# 467444_130_3_5.net
KiCad netlist of a schematic drawn in Altium Designer
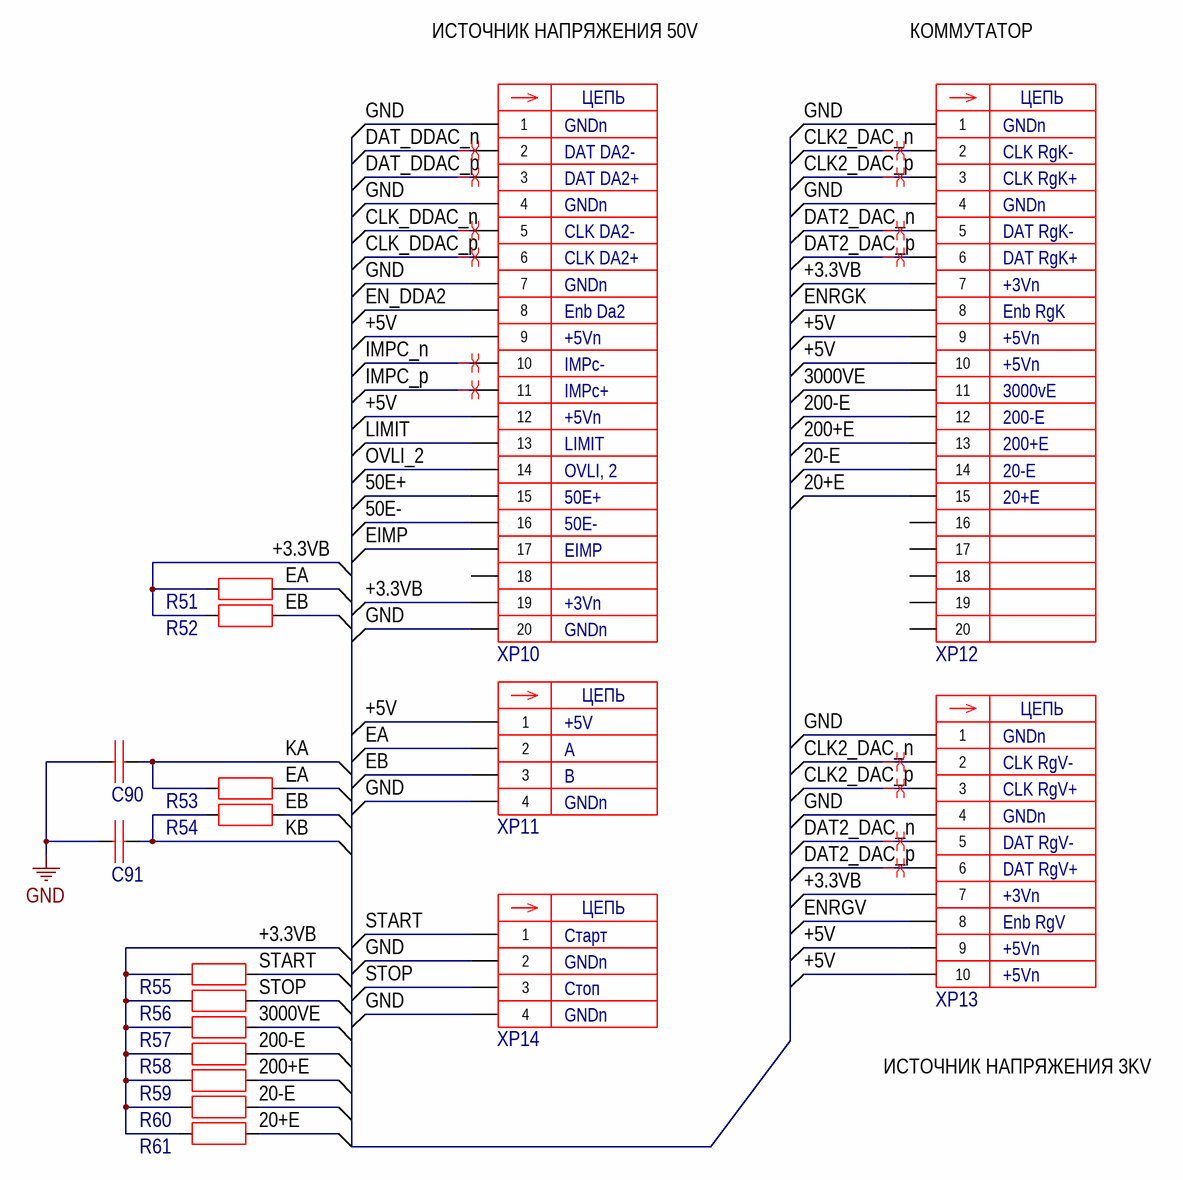
[diagram p0: УШЯИ.467444.130Э3_5.SchDoc]

(export (version "E")
  (design (tool "Eeschema 10.0.6"))
  (components
    (comp (ref "C90")
      (value "0,1 µF")
      (footprint "C_0805 [2012 Metric]")
      (description "Неполярный конденсатор")
      (fields (field (name "MANUFACTURER") "Murata") (field (name "VOLTAGE") "50V"))
      (libsource (lib "lib") (part "C_const"))
    )
    (comp (ref "C91")
      (value "0,1 µF")
      (footprint "C_0805 [2012 Metric]")
      (description "Неполярный конденсатор")
      (fields (field (name "MANUFACTURER") "Murata") (field (name "VOLTAGE") "50V"))
      (libsource (lib "lib") (part "C_const"))
    )
    (comp (ref "R51")
      (value "10k")
      (footprint "R_0805 [2012 Metric]")
      (fields (field (name "TOLERANCE") "±1%"))
      (libsource (lib "lib") (part "R_Const"))
    )
    (comp (ref "R52")
      (value "10k")
      (footprint "R_0805 [2012 Metric]")
      (fields (field (name "TOLERANCE") "±1%"))
      (libsource (lib "lib") (part "R_Const"))
    )
    (comp (ref "R53")
      (value "10k")
      (footprint "R_0805 [2012 Metric]")
      (fields (field (name "TOLERANCE") "±1%"))
      (libsource (lib "lib") (part "R_Const"))
    )
    (comp (ref "R54")
      (value "10k")
      (footprint "R_0805 [2012 Metric]")
      (fields (field (name "TOLERANCE") "±1%"))
      (libsource (lib "lib") (part "R_Const"))
    )
    (comp (ref "R55")
      (value "10k")
      (footprint "R_0805 [2012 Metric]")
      (fields (field (name "TOLERANCE") "±1%"))
      (libsource (lib "lib") (part "R_Const"))
    )
    (comp (ref "R56")
      (value "10k")
      (footprint "R_0805 [2012 Metric]")
      (fields (field (name "TOLERANCE") "±1%"))
      (libsource (lib "lib") (part "R_Const"))
    )
    (comp (ref "R57")
      (value "10k")
      (footprint "R_0805 [2012 Metric]")
      (fields (field (name "TOLERANCE") "±1%"))
      (libsource (lib "lib") (part "R_Const"))
    )
    (comp (ref "R58")
      (value "10k")
      (footprint "R_0805 [2012 Metric]")
      (fields (field (name "TOLERANCE") "±1%"))
      (libsource (lib "lib") (part "R_Const"))
    )
    (comp (ref "R59")
      (value "10k")
      (footprint "R_0805 [2012 Metric]")
      (fields (field (name "TOLERANCE") "±1%"))
      (libsource (lib "lib") (part "R_Const"))
    )
    (comp (ref "R60")
      (value "10k")
      (footprint "R_0805 [2012 Metric]")
      (fields (field (name "TOLERANCE") "±1%"))
      (libsource (lib "lib") (part "R_Const"))
    )
    (comp (ref "R61")
      (value "10k")
      (footprint "R_0805 [2012 Metric]")
      (fields (field (name "TOLERANCE") "±1%"))
      (libsource (lib "lib") (part "R_Const"))
    )
    (comp (ref "XP10")
      (value "BH2-20R")
      (footprint "BH2-20R")
      (description "Male, 20 pins, 2 rows, Right Angle, DS1014-20RF1B-B, 2 mm")
      (fields (field (name "MANUFACTURER") "Connfly electronic"))
      (libsource (lib "lib") (part "M_20"))
    )
    (comp (ref "XP11")
      (value "AMPMODU II 280371-2")
      (footprint "AMP II-280371-2")
      (description "Male, 4 pin, 1 row, Vertical, Board-to-Board, 2.54 mm")
      (fields (field (name "MANUFACTURER") "TE Connectivity"))
      (libsource (lib "lib") (part "M_4"))
    )
    (comp (ref "XP12")
      (value "BH2-20R")
      (footprint "BH2-20R")
      (description "Male, 20 pins, 2 rows, Right Angle, DS1014-20RF1B-B, 2 mm")
      (fields (field (name "MANUFACTURER") "Connfly electronic"))
      (libsource (lib "lib") (part "M_20"))
    )
    (comp (ref "XP13")
      (value "BH2-10R")
      (footprint "BH2-10R")
      (description "Male, 10 pins, 2 rows, Vertical, DS1014-10RF1B-B, 2 mm")
      (fields (field (name "MANUFACTURER") "Connfly electronic"))
      (libsource (lib "lib") (part "M_10"))
    )
    (comp (ref "XP14")
      (value "AMPMODU II 280371-2")
      (footprint "AMP II-280371-2")
      (description "Male, 4 pin, 1 row, Vertical, Board-to-Board, 2.54 mm")
      (fields (field (name "MANUFACTURER") "TE Connectivity"))
      (libsource (lib "lib") (part "M_4"))
    )
  )
  (nets
    (net (code "1") (name "/+3.3VB") (class "Default")
      (node (ref "R51") (pin "1") (pinfunction "1_1") (pintype "passive"))
      (node (ref "R52") (pin "1") (pinfunction "1_1") (pintype "passive"))
      (node (ref "R55") (pin "1") (pinfunction "1_1") (pintype "passive"))
      (node (ref "R56") (pin "1") (pinfunction "1_1") (pintype "passive"))
      (node (ref "R57") (pin "1") (pinfunction "1_1") (pintype "passive"))
      (node (ref "R58") (pin "1") (pinfunction "1_1") (pintype "passive"))
      (node (ref "R59") (pin "1") (pinfunction "1_1") (pintype "passive"))
      (node (ref "R60") (pin "1") (pinfunction "1_1") (pintype "passive"))
      (node (ref "R61") (pin "1") (pinfunction "1_1") (pintype "passive"))
      (node (ref "XP10") (pin "19") (pinfunction "19_19") (pintype "passive"))
      (node (ref "XP12") (pin "7") (pinfunction "7_7") (pintype "passive"))
      (node (ref "XP13") (pin "7") (pinfunction "7_7") (pintype "passive"))
    )
    (net (code "2") (name "/+5V") (class "Default")
      (node (ref "XP10") (pin "12") (pinfunction "12_12") (pintype "passive"))
      (node (ref "XP10") (pin "9") (pinfunction "9_9") (pintype "passive"))
      (node (ref "XP11") (pin "1") (pinfunction "1_1") (pintype "passive"))
      (node (ref "XP12") (pin "10") (pinfunction "10_10") (pintype "passive"))
      (node (ref "XP12") (pin "9") (pinfunction "9_9") (pintype "passive"))
      (node (ref "XP13") (pin "10") (pinfunction "10_10") (pintype "passive"))
      (node (ref "XP13") (pin "9") (pinfunction "9_9") (pintype "passive"))
    )
    (net (code "3") (name "/20+E") (class "Default")
      (node (ref "R61") (pin "2") (pinfunction "2_2") (pintype "passive"))
      (node (ref "XP12") (pin "15") (pinfunction "15_15") (pintype "passive"))
    )
    (net (code "4") (name "/20-E") (class "Default")
      (node (ref "R60") (pin "2") (pinfunction "2_2") (pintype "passive"))
      (node (ref "XP12") (pin "14") (pinfunction "14_14") (pintype "passive"))
    )
    (net (code "5") (name "/50E+") (class "Default")
      (node (ref "XP10") (pin "15") (pinfunction "15_15") (pintype "passive"))
    )
    (net (code "6") (name "/50E-") (class "Default")
      (node (ref "XP10") (pin "16") (pinfunction "16_16") (pintype "passive"))
    )
    (net (code "7") (name "/200+E") (class "Default")
      (node (ref "R59") (pin "2") (pinfunction "2_2") (pintype "passive"))
      (node (ref "XP12") (pin "13") (pinfunction "13_13") (pintype "passive"))
    )
    (net (code "8") (name "/200-E") (class "Default")
      (node (ref "R58") (pin "2") (pinfunction "2_2") (pintype "passive"))
      (node (ref "XP12") (pin "12") (pinfunction "12_12") (pintype "passive"))
    )
    (net (code "9") (name "/3000VE") (class "Default")
      (node (ref "R57") (pin "2") (pinfunction "2_2") (pintype "passive"))
      (node (ref "XP12") (pin "11") (pinfunction "11_11") (pintype "passive"))
    )
    (net (code "10") (name "/CLK2_DAC_n") (class "Default")
      (node (ref "XP12") (pin "2") (pinfunction "2_2") (pintype "passive"))
      (node (ref "XP13") (pin "2") (pinfunction "2_2") (pintype "passive"))
    )
    (net (code "11") (name "/CLK2_DAC_p") (class "Default")
      (node (ref "XP12") (pin "3") (pinfunction "3_3") (pintype "passive"))
      (node (ref "XP13") (pin "3") (pinfunction "3_3") (pintype "passive"))
    )
    (net (code "12") (name "/CLK_DDAC_n") (class "Default")
      (node (ref "XP10") (pin "5") (pinfunction "5_5") (pintype "passive"))
    )
    (net (code "13") (name "/CLK_DDAC_p") (class "Default")
      (node (ref "XP10") (pin "6") (pinfunction "6_6") (pintype "passive"))
    )
    (net (code "14") (name "/DAT2_DAC_n") (class "Default")
      (node (ref "XP12") (pin "5") (pinfunction "5_5") (pintype "passive"))
      (node (ref "XP13") (pin "5") (pinfunction "5_5") (pintype "passive"))
    )
    (net (code "15") (name "/DAT2_DAC_p") (class "Default")
      (node (ref "XP12") (pin "6") (pinfunction "6_6") (pintype "passive"))
      (node (ref "XP13") (pin "6") (pinfunction "6_6") (pintype "passive"))
    )
    (net (code "16") (name "/DAT_DDAC_n") (class "Default")
      (node (ref "XP10") (pin "2") (pinfunction "2_2") (pintype "passive"))
    )
    (net (code "17") (name "/DAT_DDAC_p") (class "Default")
      (node (ref "XP10") (pin "3") (pinfunction "3_3") (pintype "passive"))
    )
    (net (code "18") (name "/EA") (class "Default")
      (node (ref "R51") (pin "2") (pinfunction "2_2") (pintype "passive"))
      (node (ref "R53") (pin "2") (pinfunction "2_2") (pintype "passive"))
      (node (ref "XP11") (pin "2") (pinfunction "2_2") (pintype "passive"))
    )
    (net (code "19") (name "/EB") (class "Default")
      (node (ref "R52") (pin "2") (pinfunction "2_2") (pintype "passive"))
      (node (ref "R54") (pin "2") (pinfunction "2_2") (pintype "passive"))
      (node (ref "XP11") (pin "3") (pinfunction "3_3") (pintype "passive"))
    )
    (net (code "20") (name "/EIMP") (class "Default")
      (node (ref "XP10") (pin "17") (pinfunction "17_17") (pintype "passive"))
    )
    (net (code "21") (name "/ENRGK") (class "Default")
      (node (ref "XP12") (pin "8") (pinfunction "8_8") (pintype "passive"))
    )
    (net (code "22") (name "/ENRGV") (class "Default")
      (node (ref "XP13") (pin "8") (pinfunction "8_8") (pintype "passive"))
    )
    (net (code "23") (name "/EN_DDA2") (class "Default")
      (node (ref "XP10") (pin "8") (pinfunction "8_8") (pintype "passive"))
    )
    (net (code "24") (name "/IMPC_n") (class "Default")
      (node (ref "XP10") (pin "10") (pinfunction "10_10") (pintype "passive"))
    )
    (net (code "25") (name "/IMPC_p") (class "Default")
      (node (ref "XP10") (pin "11") (pinfunction "11_11") (pintype "passive"))
    )
    (net (code "26") (name "/KA") (class "Default")
      (node (ref "C90") (pin "1") (pinfunction "1_1") (pintype "passive"))
      (node (ref "R53") (pin "1") (pinfunction "1_1") (pintype "passive"))
    )
    (net (code "27") (name "/KB") (class "Default")
      (node (ref "C91") (pin "1") (pinfunction "1_1") (pintype "passive"))
      (node (ref "R54") (pin "1") (pinfunction "1_1") (pintype "passive"))
    )
    (net (code "28") (name "/LIMIT") (class "Default")
      (node (ref "XP10") (pin "13") (pinfunction "13_13") (pintype "passive"))
    )
    (net (code "29") (name "/OVLI_2") (class "Default")
      (node (ref "XP10") (pin "14") (pinfunction "14_14") (pintype "passive"))
    )
    (net (code "30") (name "/START") (class "Default")
      (node (ref "R55") (pin "2") (pinfunction "2_2") (pintype "passive"))
      (node (ref "XP14") (pin "1") (pinfunction "1_1") (pintype "passive"))
    )
    (net (code "31") (name "/STOP") (class "Default")
      (node (ref "R56") (pin "2") (pinfunction "2_2") (pintype "passive"))
      (node (ref "XP14") (pin "3") (pinfunction "3_3") (pintype "passive"))
    )
    (net (code "32") (name "GND") (class "Default")
      (node (ref "C90") (pin "2") (pinfunction "2_2") (pintype "passive"))
      (node (ref "C91") (pin "2") (pinfunction "2_2") (pintype "passive"))
      (node (ref "XP10") (pin "1") (pinfunction "1_1") (pintype "passive"))
      (node (ref "XP10") (pin "20") (pinfunction "20_20") (pintype "passive"))
      (node (ref "XP10") (pin "4") (pinfunction "4_4") (pintype "passive"))
      (node (ref "XP10") (pin "7") (pinfunction "7_7") (pintype "passive"))
      (node (ref "XP11") (pin "4") (pinfunction "4_4") (pintype "passive"))
      (node (ref "XP12") (pin "1") (pinfunction "1_1") (pintype "passive"))
      (node (ref "XP12") (pin "4") (pinfunction "4_4") (pintype "passive"))
      (node (ref "XP13") (pin "1") (pinfunction "1_1") (pintype "passive"))
      (node (ref "XP13") (pin "4") (pinfunction "4_4") (pintype "passive"))
      (node (ref "XP14") (pin "2") (pinfunction "2_2") (pintype "passive"))
      (node (ref "XP14") (pin "4") (pinfunction "4_4") (pintype "passive"))
    )
    (net (code "33") (name "unconnected-(XP10-Pad18)") (class "Default")
      (node (ref "XP10") (pin "18") (pinfunction "18_18") (pintype "passive"))
    )
    (net (code "34") (name "unconnected-(XP12-Pad16)") (class "Default")
      (node (ref "XP12") (pin "16") (pinfunction "16_16") (pintype "passive"))
    )
    (net (code "35") (name "unconnected-(XP12-Pad17)") (class "Default")
      (node (ref "XP12") (pin "17") (pinfunction "17_17") (pintype "passive"))
    )
    (net (code "36") (name "unconnected-(XP12-Pad18)") (class "Default")
      (node (ref "XP12") (pin "18") (pinfunction "18_18") (pintype "passive"))
    )
    (net (code "37") (name "unconnected-(XP12-Pad19)") (class "Default")
      (node (ref "XP12") (pin "19") (pinfunction "19_19") (pintype "passive"))
    )
    (net (code "38") (name "unconnected-(XP12-Pad20)") (class "Default")
      (node (ref "XP12") (pin "20") (pinfunction "20_20") (pintype "passive"))
    )
  )
)
